# BPB_v16.net
KiCad netlist of a schematic drawn in EAGLE
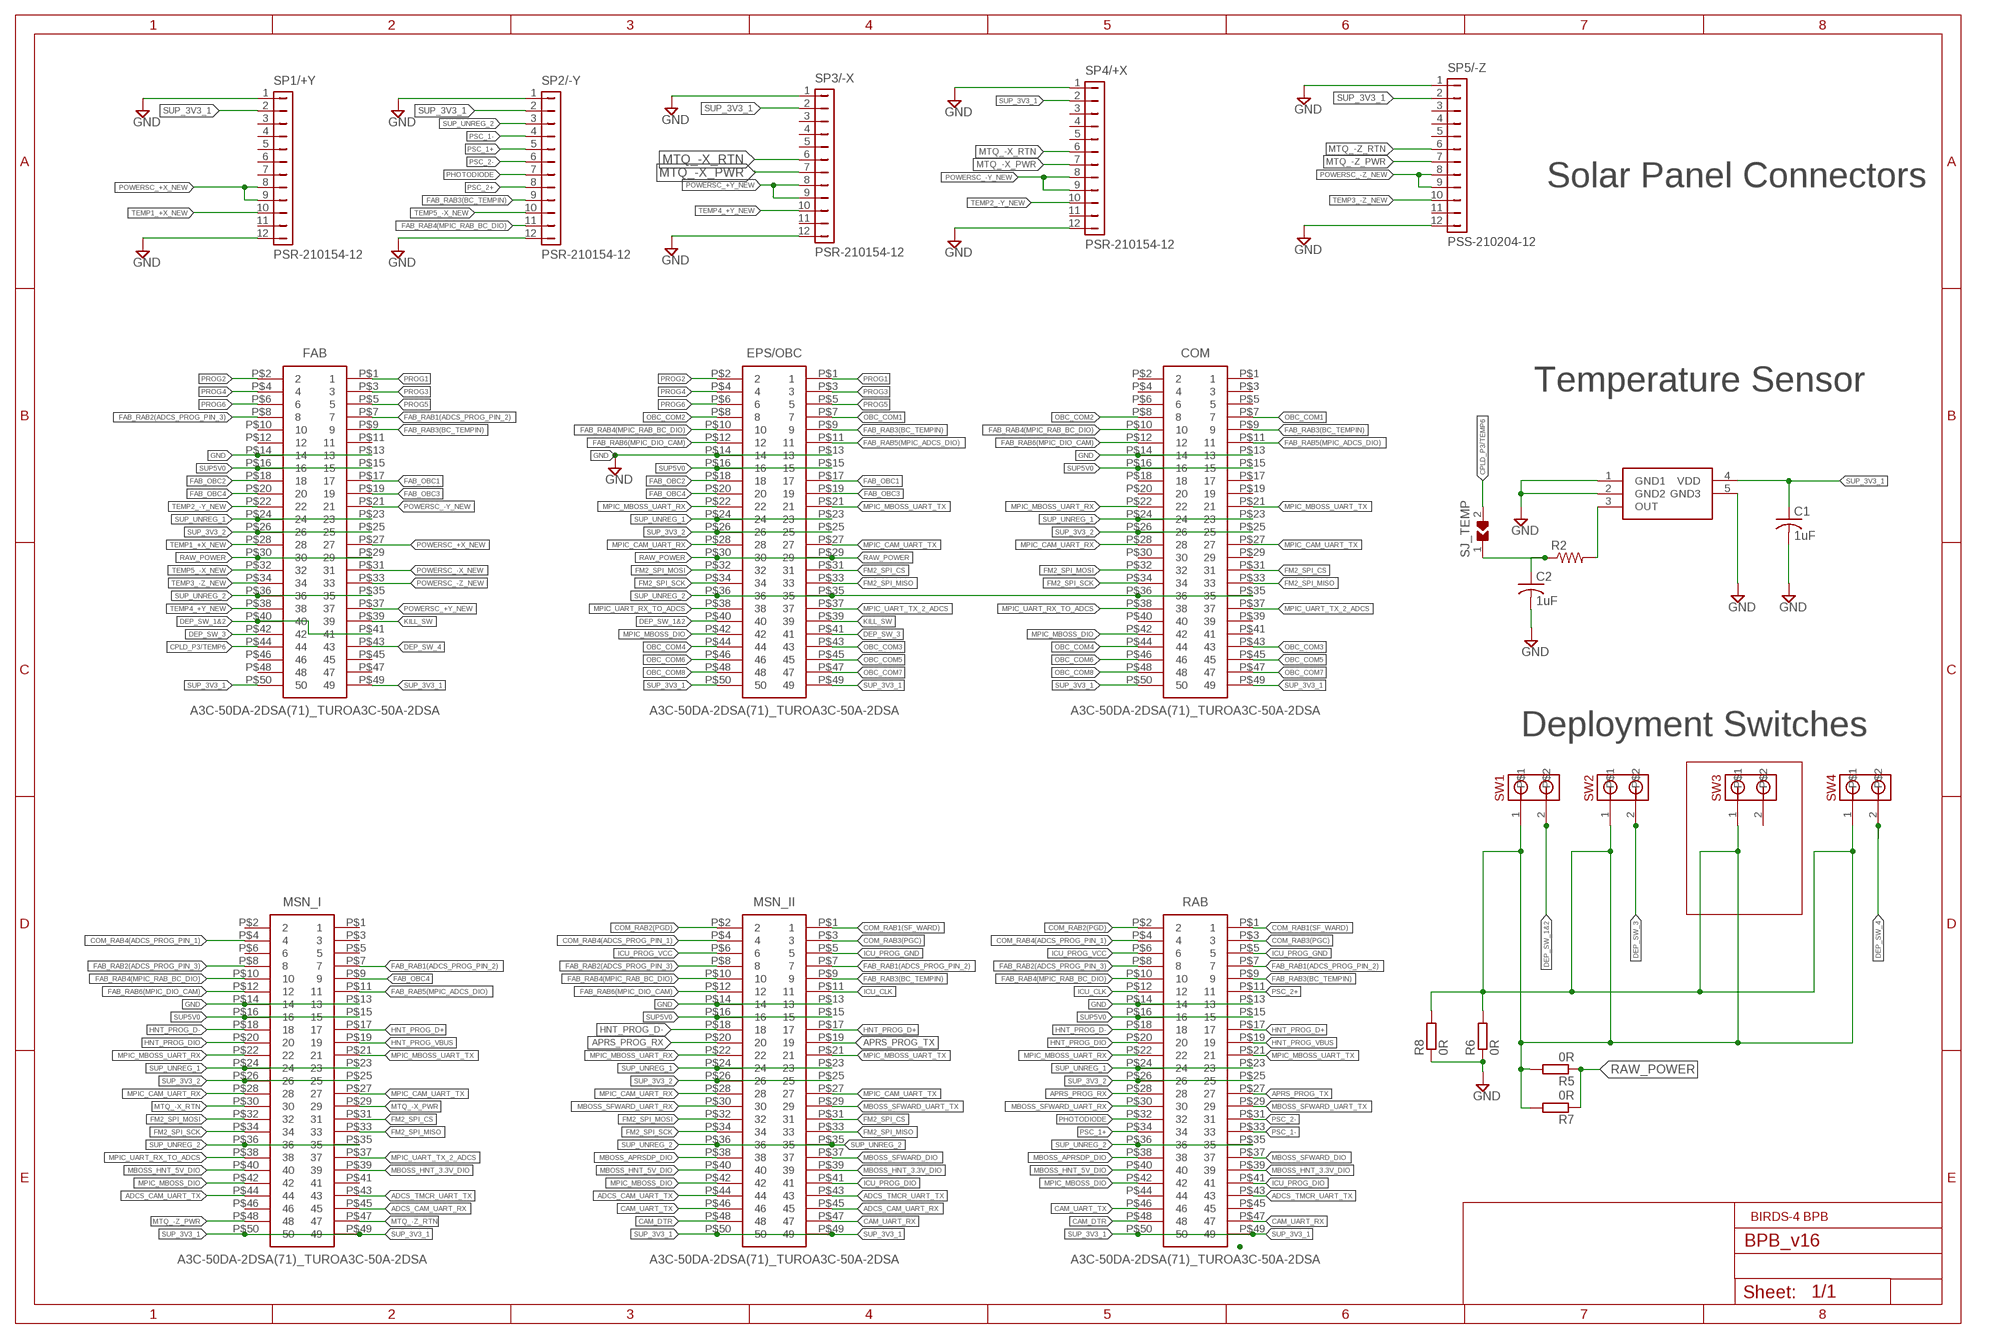
[diagram p0: schematic, sheet 1]

(export (version "E")
  (design (tool "Eeschema 10.0.6"))
  (components
    (comp (ref "C1")
      (value "1uF")
      (footprint "eagle-import:C0603")
      (libsource (lib "eagle-import") (part "C-USC0603"))
    )
    (comp (ref "C2")
      (value "1uF")
      (footprint "eagle-import:C0603")
      (libsource (lib "eagle-import") (part "C-USC0603"))
    )
    (comp (ref "COM")
      (value "A3C-50DA-2DSA(71)_TUROA3C-50A-2DSA")
      (footprint "eagle-import:SHDR50W60P200_2X25_5000X400X44_TR")
      (libsource (lib "eagle-import") (part "A3C-50DA-2DSA(71)_TUROA3C-50A-2DSA"))
    )
    (comp (ref "EPS/OBC")
      (value "A3C-50DA-2DSA(71)_TUROA3C-50A-2DSA")
      (footprint "eagle-import:SHDR50W60P200_2X25_5000X400X44_TR")
      (libsource (lib "eagle-import") (part "A3C-50DA-2DSA(71)_TUROA3C-50A-2DSA"))
    )
    (comp (ref "FAB")
      (value "A3C-50DA-2DSA(71)_TUROA3C-50A-2DSA")
      (footprint "eagle-import:SHDR50W60P200_2X25_5000X400X44_TR")
      (libsource (lib "eagle-import") (part "A3C-50DA-2DSA(71)_TUROA3C-50A-2DSA"))
    )
    (comp (ref "MSN_I")
      (value "A3C-50DA-2DSA(71)_TUROA3C-50A-2DSA")
      (footprint "eagle-import:SHDR50W60P200_2X25_5000X400X44_TR")
      (libsource (lib "eagle-import") (part "A3C-50DA-2DSA(71)_TUROA3C-50A-2DSA"))
    )
    (comp (ref "MSN_II")
      (value "A3C-50DA-2DSA(71)_TUROA3C-50A-2DSA")
      (footprint "eagle-import:SHDR50W60P200_2X25_5000X400X44_TR")
      (libsource (lib "eagle-import") (part "A3C-50DA-2DSA(71)_TUROA3C-50A-2DSA"))
    )
    (comp (ref "R2")
      (value "R-US_R0402")
      (footprint "eagle-import:R0402")
      (libsource (lib "eagle-import") (part "R-US_R0402"))
    )
    (comp (ref "R5")
      (value "0R")
      (footprint "eagle-import:R3216")
      (libsource (lib "eagle-import") (part "RR3216"))
    )
    (comp (ref "R6")
      (value "0R")
      (footprint "eagle-import:R3216")
      (libsource (lib "eagle-import") (part "RR3216"))
    )
    (comp (ref "R7")
      (value "0R")
      (footprint "eagle-import:R3216")
      (libsource (lib "eagle-import") (part "RR3216"))
    )
    (comp (ref "R8")
      (value "0R")
      (footprint "eagle-import:R3216")
      (libsource (lib "eagle-import") (part "RR3216"))
    )
    (comp (ref "RAB")
      (value "A3C-50DA-2DSA(71)_TUROA3C-50A-2DSA")
      (footprint "eagle-import:SHDR50W60P200_2X25_5000X400X44_TR")
      (libsource (lib "eagle-import") (part "A3C-50DA-2DSA(71)_TUROA3C-50A-2DSA"))
    )
    (comp (ref "SJ_TEMP")
      (value "SJ_BY_TURO")
      (footprint "eagle-import:SJ_TURO")
      (libsource (lib "eagle-import") (part "SJ_BY_TURO"))
    )
    (comp (ref "SP1/+Y")
      (value "PSR-210154-12")
      (footprint "eagle-import:PIN1X12_90")
      (libsource (lib "eagle-import") (part "PSR-210154-12"))
    )
    (comp (ref "SP2/-Y")
      (value "PSR-210154-12")
      (footprint "eagle-import:PIN1X12_90")
      (libsource (lib "eagle-import") (part "PSR-210154-12"))
    )
    (comp (ref "SP3/-X")
      (value "PSR-210154-12")
      (footprint "eagle-import:PIN1X12_90")
      (libsource (lib "eagle-import") (part "PSR-210154-12"))
    )
    (comp (ref "SP4/+X")
      (value "PSR-210154-12")
      (footprint "eagle-import:PIN1X12_90")
      (libsource (lib "eagle-import") (part "PSR-210154-12"))
    )
    (comp (ref "SP5/-Z")
      (value "PSS-210204-12")
      (footprint "eagle-import:PIN1X12")
      (libsource (lib "eagle-import") (part "PSS-210204-12"))
    )
    (comp (ref "SW1")
      (value "MOLEX-CONN-2-0554600272")
      (footprint "eagle-import:MOLEX-CONN-2-BIRDS")
      (libsource (lib "eagle-import") (part "MOLEX-CONN-2-0554600272"))
    )
    (comp (ref "SW2")
      (value "MOLEX-CONN-2-0554600272")
      (footprint "eagle-import:MOLEX-CONN-2-BIRDS")
      (libsource (lib "eagle-import") (part "MOLEX-CONN-2-0554600272"))
    )
    (comp (ref "SW3")
      (value "MOLEX-CONN-2-0554600272")
      (footprint "eagle-import:MOLEX-CONN-2-BIRDS")
      (libsource (lib "eagle-import") (part "MOLEX-CONN-2-0554600272"))
    )
    (comp (ref "SW4")
      (value "MOLEX-CONN-2-0554600272")
      (footprint "eagle-import:MOLEX-CONN-2-BIRDS")
      (libsource (lib "eagle-import") (part "MOLEX-CONN-2-0554600272"))
    )
    (comp (ref "U$3")
      (value "LMT84DCKT")
      (footprint "eagle-import:SOT65P210X110-5N")
      (fields (field (name "RS_PART_NUMBER") "8115860"))
      (libsource (lib "eagle-import") (part "LMT84DCKT"))
    )
  )
  (nets
    (net (code "1") (name "ADCS_CAM_UART_RX") (class "Default")
      (node (ref "MSN_I") (pin "P$45") (pinfunction "45_P$45") (pintype "passive"))
      (node (ref "MSN_II") (pin "P$45") (pinfunction "45_P$45") (pintype "passive"))
    )
    (net (code "2") (name "ADCS_CAM_UART_TX") (class "Default")
      (node (ref "MSN_I") (pin "P$44") (pinfunction "44_P$44") (pintype "passive"))
      (node (ref "MSN_II") (pin "P$44") (pinfunction "44_P$44") (pintype "passive"))
    )
    (net (code "3") (name "ADCS_TMCR_UART_TX") (class "Default")
      (node (ref "MSN_I") (pin "P$43") (pinfunction "43_P$43") (pintype "passive"))
      (node (ref "MSN_II") (pin "P$43") (pinfunction "43_P$43") (pintype "passive"))
      (node (ref "RAB") (pin "P$43") (pinfunction "43_P$43") (pintype "passive"))
    )
    (net (code "4") (name "APRS_PROG_RX") (class "Default")
      (node (ref "MSN_II") (pin "P$20") (pinfunction "20_P$20") (pintype "passive"))
      (node (ref "RAB") (pin "P$28") (pinfunction "28_P$28") (pintype "passive"))
    )
    (net (code "5") (name "APRS_PROG_TX") (class "Default")
      (node (ref "MSN_II") (pin "P$19") (pinfunction "19_P$19") (pintype "passive"))
      (node (ref "RAB") (pin "P$27") (pinfunction "27_P$27") (pintype "passive"))
    )
    (net (code "6") (name "CAM_DTR") (class "Default")
      (node (ref "MSN_II") (pin "P$48") (pinfunction "48_P$48") (pintype "passive"))
      (node (ref "RAB") (pin "P$48") (pinfunction "48_P$48") (pintype "passive"))
    )
    (net (code "7") (name "CAM_UART_RX") (class "Default")
      (node (ref "MSN_II") (pin "P$47") (pinfunction "47_P$47") (pintype "passive"))
      (node (ref "RAB") (pin "P$47") (pinfunction "47_P$47") (pintype "passive"))
    )
    (net (code "8") (name "CAM_UART_TX") (class "Default")
      (node (ref "MSN_II") (pin "P$46") (pinfunction "46_P$46") (pintype "passive"))
      (node (ref "RAB") (pin "P$46") (pinfunction "46_P$46") (pintype "passive"))
    )
    (net (code "9") (name "COM_RAB1(SF_WARD)") (class "Default")
      (node (ref "MSN_II") (pin "P$1") (pinfunction "1_P$1") (pintype "passive"))
      (node (ref "RAB") (pin "P$1") (pinfunction "1_P$1") (pintype "passive"))
    )
    (net (code "10") (name "COM_RAB2(PGD)") (class "Default")
      (node (ref "MSN_II") (pin "P$2") (pinfunction "2_P$2") (pintype "passive"))
      (node (ref "RAB") (pin "P$2") (pinfunction "2_P$2") (pintype "passive"))
    )
    (net (code "11") (name "COM_RAB3(PGC)") (class "Default")
      (node (ref "MSN_II") (pin "P$3") (pinfunction "3_P$3") (pintype "passive"))
      (node (ref "RAB") (pin "P$3") (pinfunction "3_P$3") (pintype "passive"))
    )
    (net (code "12") (name "COM_RAB4(ADCS_PROG_PIN_1)") (class "Default")
      (node (ref "MSN_I") (pin "P$4") (pinfunction "4_P$4") (pintype "passive"))
      (node (ref "MSN_II") (pin "P$4") (pinfunction "4_P$4") (pintype "passive"))
      (node (ref "RAB") (pin "P$4") (pinfunction "4_P$4") (pintype "passive"))
    )
    (net (code "13") (name "CPLD_P3{slash}TEMP6") (class "Default")
      (node (ref "FAB") (pin "P$44") (pinfunction "44_P$44") (pintype "passive"))
      (node (ref "SJ_TEMP") (pin "2") (pinfunction "2_2") (pintype "passive"))
    )
    (net (code "14") (name "DEP_SW_1&2") (class "Default")
      (node (ref "EPS/OBC") (pin "P$40") (pinfunction "40_P$40") (pintype "passive"))
      (node (ref "FAB") (pin "P$40") (pinfunction "40_P$40") (pintype "passive"))
      (node (ref "FAB") (pin "P$41") (pinfunction "41_P$41") (pintype "passive"))
      (node (ref "SW1") (pin "2") (pinfunction "P$2_2") (pintype "bidirectional"))
    )
    (net (code "15") (name "DEP_SW_3") (class "Default")
      (node (ref "EPS/OBC") (pin "P$41") (pinfunction "41_P$41") (pintype "passive"))
      (node (ref "FAB") (pin "P$42") (pinfunction "42_P$42") (pintype "passive"))
      (node (ref "SW2") (pin "2") (pinfunction "P$2_2") (pintype "bidirectional"))
    )
    (net (code "16") (name "DEP_SW_4") (class "Default")
      (node (ref "FAB") (pin "P$43") (pinfunction "43_P$43") (pintype "passive"))
      (node (ref "SW4") (pin "2") (pinfunction "P$2_2") (pintype "bidirectional"))
    )
    (net (code "17") (name "FAB_OBC1") (class "Default")
      (node (ref "EPS/OBC") (pin "P$17") (pinfunction "17_P$17") (pintype "passive"))
      (node (ref "FAB") (pin "P$17") (pinfunction "17_P$17") (pintype "passive"))
    )
    (net (code "18") (name "FAB_OBC2") (class "Default")
      (node (ref "EPS/OBC") (pin "P$18") (pinfunction "18_P$18") (pintype "passive"))
      (node (ref "FAB") (pin "P$18") (pinfunction "18_P$18") (pintype "passive"))
    )
    (net (code "19") (name "FAB_OBC3") (class "Default")
      (node (ref "EPS/OBC") (pin "P$19") (pinfunction "19_P$19") (pintype "passive"))
      (node (ref "FAB") (pin "P$19") (pinfunction "19_P$19") (pintype "passive"))
    )
    (net (code "20") (name "FAB_OBC4") (class "Default")
      (node (ref "EPS/OBC") (pin "P$20") (pinfunction "20_P$20") (pintype "passive"))
      (node (ref "FAB") (pin "P$20") (pinfunction "20_P$20") (pintype "passive"))
      (node (ref "MSN_I") (pin "P$9") (pinfunction "9_P$9") (pintype "passive"))
    )
    (net (code "21") (name "FAB_RAB1(ADCS_PROG_PIN_2)") (class "Default")
      (node (ref "FAB") (pin "P$7") (pinfunction "7_P$7") (pintype "passive"))
      (node (ref "MSN_I") (pin "P$7") (pinfunction "7_P$7") (pintype "passive"))
      (node (ref "MSN_II") (pin "P$7") (pinfunction "7_P$7") (pintype "passive"))
      (node (ref "RAB") (pin "P$7") (pinfunction "7_P$7") (pintype "passive"))
    )
    (net (code "22") (name "FAB_RAB2(ADCS_PROG_PIN_3)") (class "Default")
      (node (ref "FAB") (pin "P$8") (pinfunction "8_P$8") (pintype "passive"))
      (node (ref "MSN_I") (pin "P$8") (pinfunction "8_P$8") (pintype "passive"))
      (node (ref "MSN_II") (pin "P$8") (pinfunction "8_P$8") (pintype "passive"))
      (node (ref "RAB") (pin "P$8") (pinfunction "8_P$8") (pintype "passive"))
    )
    (net (code "23") (name "FAB_RAB3(BC_TEMPIN)") (class "Default")
      (node (ref "COM") (pin "P$9") (pinfunction "9_P$9") (pintype "passive"))
      (node (ref "EPS/OBC") (pin "P$9") (pinfunction "9_P$9") (pintype "passive"))
      (node (ref "FAB") (pin "P$9") (pinfunction "9_P$9") (pintype "passive"))
      (node (ref "MSN_II") (pin "P$9") (pinfunction "9_P$9") (pintype "passive"))
      (node (ref "RAB") (pin "P$9") (pinfunction "9_P$9") (pintype "passive"))
      (node (ref "SP2/-Y") (pin "9") (pinfunction "9_9") (pintype "passive"))
    )
    (net (code "24") (name "FAB_RAB4(MPIC_RAB_BC_DIO)") (class "Default")
      (node (ref "COM") (pin "P$10") (pinfunction "10_P$10") (pintype "passive"))
      (node (ref "EPS/OBC") (pin "P$10") (pinfunction "10_P$10") (pintype "passive"))
      (node (ref "MSN_I") (pin "P$10") (pinfunction "10_P$10") (pintype "passive"))
      (node (ref "MSN_II") (pin "P$10") (pinfunction "10_P$10") (pintype "passive"))
      (node (ref "RAB") (pin "P$10") (pinfunction "10_P$10") (pintype "passive"))
      (node (ref "SP2/-Y") (pin "11") (pinfunction "11_11") (pintype "passive"))
    )
    (net (code "25") (name "FAB_RAB5(MPIC_ADCS_DIO)") (class "Default")
      (node (ref "COM") (pin "P$11") (pinfunction "11_P$11") (pintype "passive"))
      (node (ref "EPS/OBC") (pin "P$11") (pinfunction "11_P$11") (pintype "passive"))
      (node (ref "MSN_I") (pin "P$11") (pinfunction "11_P$11") (pintype "passive"))
    )
    (net (code "26") (name "FAB_RAB6(MPIC_DIO_CAM)") (class "Default")
      (node (ref "COM") (pin "P$12") (pinfunction "12_P$12") (pintype "passive"))
      (node (ref "EPS/OBC") (pin "P$12") (pinfunction "12_P$12") (pintype "passive"))
      (node (ref "MSN_I") (pin "P$12") (pinfunction "12_P$12") (pintype "passive"))
      (node (ref "MSN_II") (pin "P$12") (pinfunction "12_P$12") (pintype "passive"))
    )
    (net (code "27") (name "FM2_SPI_CS") (class "Default")
      (node (ref "COM") (pin "P$31") (pinfunction "31_P$31") (pintype "passive"))
      (node (ref "EPS/OBC") (pin "P$31") (pinfunction "31_P$31") (pintype "passive"))
      (node (ref "MSN_I") (pin "P$31") (pinfunction "31_P$31") (pintype "passive"))
      (node (ref "MSN_II") (pin "P$31") (pinfunction "31_P$31") (pintype "passive"))
    )
    (net (code "28") (name "FM2_SPI_MISO") (class "Default")
      (node (ref "COM") (pin "P$33") (pinfunction "33_P$33") (pintype "passive"))
      (node (ref "EPS/OBC") (pin "P$33") (pinfunction "33_P$33") (pintype "passive"))
      (node (ref "MSN_I") (pin "P$33") (pinfunction "33_P$33") (pintype "passive"))
      (node (ref "MSN_II") (pin "P$33") (pinfunction "33_P$33") (pintype "passive"))
    )
    (net (code "29") (name "FM2_SPI_MOSI") (class "Default")
      (node (ref "COM") (pin "P$32") (pinfunction "32_P$32") (pintype "passive"))
      (node (ref "EPS/OBC") (pin "P$32") (pinfunction "32_P$32") (pintype "passive"))
      (node (ref "MSN_I") (pin "P$32") (pinfunction "32_P$32") (pintype "passive"))
      (node (ref "MSN_II") (pin "P$32") (pinfunction "32_P$32") (pintype "passive"))
    )
    (net (code "30") (name "FM2_SPI_SCK") (class "Default")
      (node (ref "COM") (pin "P$34") (pinfunction "34_P$34") (pintype "passive"))
      (node (ref "EPS/OBC") (pin "P$34") (pinfunction "34_P$34") (pintype "passive"))
      (node (ref "MSN_I") (pin "P$34") (pinfunction "34_P$34") (pintype "passive"))
      (node (ref "MSN_II") (pin "P$34") (pinfunction "34_P$34") (pintype "passive"))
    )
    (net (code "31") (name "GND") (class "Default")
      (node (ref "C1") (pin "2") (pinfunction "2_2") (pintype "passive"))
      (node (ref "C2") (pin "2") (pinfunction "2_2") (pintype "passive"))
      (node (ref "COM") (pin "P$13") (pinfunction "13_P$13") (pintype "passive"))
      (node (ref "COM") (pin "P$14") (pinfunction "14_P$14") (pintype "passive"))
      (node (ref "EPS/OBC") (pin "P$13") (pinfunction "13_P$13") (pintype "passive"))
      (node (ref "EPS/OBC") (pin "P$14") (pinfunction "14_P$14") (pintype "passive"))
      (node (ref "FAB") (pin "P$13") (pinfunction "13_P$13") (pintype "passive"))
      (node (ref "FAB") (pin "P$14") (pinfunction "14_P$14") (pintype "passive"))
      (node (ref "MSN_I") (pin "P$13") (pinfunction "13_P$13") (pintype "passive"))
      (node (ref "MSN_I") (pin "P$14") (pinfunction "14_P$14") (pintype "passive"))
      (node (ref "MSN_II") (pin "P$13") (pinfunction "13_P$13") (pintype "passive"))
      (node (ref "MSN_II") (pin "P$14") (pinfunction "14_P$14") (pintype "passive"))
      (node (ref "R6") (pin "1") (pinfunction "1_1") (pintype "passive"))
      (node (ref "R8") (pin "1") (pinfunction "1_1") (pintype "passive"))
      (node (ref "RAB") (pin "P$13") (pinfunction "13_P$13") (pintype "passive"))
      (node (ref "RAB") (pin "P$14") (pinfunction "14_P$14") (pintype "passive"))
      (node (ref "SP1/+Y") (pin "1") (pinfunction "1_1") (pintype "passive"))
      (node (ref "SP1/+Y") (pin "12") (pinfunction "12_12") (pintype "passive"))
      (node (ref "SP2/-Y") (pin "1") (pinfunction "1_1") (pintype "passive"))
      (node (ref "SP2/-Y") (pin "12") (pinfunction "12_12") (pintype "passive"))
      (node (ref "SP3/-X") (pin "1") (pinfunction "1_1") (pintype "passive"))
      (node (ref "SP3/-X") (pin "12") (pinfunction "12_12") (pintype "passive"))
      (node (ref "SP4/+X") (pin "1") (pinfunction "1_1") (pintype "passive"))
      (node (ref "SP4/+X") (pin "12") (pinfunction "12_12") (pintype "passive"))
      (node (ref "SP5/-Z") (pin "1") (pinfunction "1_1") (pintype "passive"))
      (node (ref "SP5/-Z") (pin "12") (pinfunction "12_12") (pintype "passive"))
      (node (ref "U$3") (pin "1") (pinfunction "GND1_1") (pintype "power_in"))
      (node (ref "U$3") (pin "2") (pinfunction "GND2_2") (pintype "power_in"))
      (node (ref "U$3") (pin "5") (pinfunction "GND3_5") (pintype "power_in"))
    )
    (net (code "32") (name "HNT_PROG_D+") (class "Default")
      (node (ref "MSN_I") (pin "P$17") (pinfunction "17_P$17") (pintype "passive"))
      (node (ref "MSN_II") (pin "P$17") (pinfunction "17_P$17") (pintype "passive"))
      (node (ref "RAB") (pin "P$17") (pinfunction "17_P$17") (pintype "passive"))
    )
    (net (code "33") (name "HNT_PROG_D-") (class "Default")
      (node (ref "MSN_I") (pin "P$18") (pinfunction "18_P$18") (pintype "passive"))
      (node (ref "MSN_II") (pin "P$18") (pinfunction "18_P$18") (pintype "passive"))
      (node (ref "RAB") (pin "P$18") (pinfunction "18_P$18") (pintype "passive"))
    )
    (net (code "34") (name "HNT_PROG_DIO") (class "Default")
      (node (ref "MSN_I") (pin "P$20") (pinfunction "20_P$20") (pintype "passive"))
      (node (ref "RAB") (pin "P$20") (pinfunction "20_P$20") (pintype "passive"))
    )
    (net (code "35") (name "HNT_PROG_VBUS") (class "Default")
      (node (ref "MSN_I") (pin "P$19") (pinfunction "19_P$19") (pintype "passive"))
      (node (ref "RAB") (pin "P$19") (pinfunction "19_P$19") (pintype "passive"))
    )
    (net (code "36") (name "ICU_CLK") (class "Default")
      (node (ref "MSN_II") (pin "P$11") (pinfunction "11_P$11") (pintype "passive"))
      (node (ref "RAB") (pin "P$12") (pinfunction "12_P$12") (pintype "passive"))
    )
    (net (code "37") (name "ICU_PROG_DIO") (class "Default")
      (node (ref "MSN_II") (pin "P$41") (pinfunction "41_P$41") (pintype "passive"))
      (node (ref "RAB") (pin "P$41") (pinfunction "41_P$41") (pintype "passive"))
    )
    (net (code "38") (name "ICU_PROG_GND") (class "Default")
      (node (ref "MSN_II") (pin "P$5") (pinfunction "5_P$5") (pintype "passive"))
      (node (ref "RAB") (pin "P$5") (pinfunction "5_P$5") (pintype "passive"))
    )
    (net (code "39") (name "ICU_PROG_VCC") (class "Default")
      (node (ref "MSN_II") (pin "P$6") (pinfunction "6_P$6") (pintype "passive"))
      (node (ref "RAB") (pin "P$6") (pinfunction "6_P$6") (pintype "passive"))
    )
    (net (code "40") (name "KILL_SW") (class "Default")
      (node (ref "EPS/OBC") (pin "P$39") (pinfunction "39_P$39") (pintype "passive"))
      (node (ref "FAB") (pin "P$39") (pinfunction "39_P$39") (pintype "passive"))
    )
    (net (code "41") (name "MBOSS_APRSDP_DIO") (class "Default")
      (node (ref "MSN_II") (pin "P$38") (pinfunction "38_P$38") (pintype "passive"))
      (node (ref "RAB") (pin "P$38") (pinfunction "38_P$38") (pintype "passive"))
    )
    (net (code "42") (name "MBOSS_HNT_3.3V_DIO") (class "Default")
      (node (ref "MSN_I") (pin "P$39") (pinfunction "39_P$39") (pintype "passive"))
      (node (ref "MSN_II") (pin "P$39") (pinfunction "39_P$39") (pintype "passive"))
      (node (ref "RAB") (pin "P$39") (pinfunction "39_P$39") (pintype "passive"))
    )
    (net (code "43") (name "MBOSS_HNT_5V_DIO") (class "Default")
      (node (ref "MSN_I") (pin "P$40") (pinfunction "40_P$40") (pintype "passive"))
      (node (ref "MSN_II") (pin "P$40") (pinfunction "40_P$40") (pintype "passive"))
      (node (ref "RAB") (pin "P$40") (pinfunction "40_P$40") (pintype "passive"))
    )
    (net (code "44") (name "MBOSS_SFWARD_DIO") (class "Default")
      (node (ref "MSN_II") (pin "P$37") (pinfunction "37_P$37") (pintype "passive"))
      (node (ref "RAB") (pin "P$37") (pinfunction "37_P$37") (pintype "passive"))
    )
    (net (code "45") (name "MBOSS_SFWARD_UART_RX") (class "Default")
      (node (ref "MSN_II") (pin "P$30") (pinfunction "30_P$30") (pintype "passive"))
      (node (ref "RAB") (pin "P$30") (pinfunction "30_P$30") (pintype "passive"))
    )
    (net (code "46") (name "MBOSS_SFWARD_UART_TX") (class "Default")
      (node (ref "MSN_II") (pin "P$29") (pinfunction "29_P$29") (pintype "passive"))
      (node (ref "RAB") (pin "P$29") (pinfunction "29_P$29") (pintype "passive"))
    )
    (net (code "47") (name "MPIC_CAM_UART_RX") (class "Default")
      (node (ref "COM") (pin "P$28") (pinfunction "28_P$28") (pintype "passive"))
      (node (ref "EPS/OBC") (pin "P$28") (pinfunction "28_P$28") (pintype "passive"))
      (node (ref "MSN_I") (pin "P$28") (pinfunction "28_P$28") (pintype "passive"))
      (node (ref "MSN_II") (pin "P$28") (pinfunction "28_P$28") (pintype "passive"))
    )
    (net (code "48") (name "MPIC_CAM_UART_TX") (class "Default")
      (node (ref "COM") (pin "P$27") (pinfunction "27_P$27") (pintype "passive"))
      (node (ref "EPS/OBC") (pin "P$27") (pinfunction "27_P$27") (pintype "passive"))
      (node (ref "MSN_I") (pin "P$27") (pinfunction "27_P$27") (pintype "passive"))
      (node (ref "MSN_II") (pin "P$27") (pinfunction "27_P$27") (pintype "passive"))
    )
    (net (code "49") (name "MPIC_MBOSS_DIO") (class "Default")
      (node (ref "COM") (pin "P$42") (pinfunction "42_P$42") (pintype "passive"))
      (node (ref "EPS/OBC") (pin "P$42") (pinfunction "42_P$42") (pintype "passive"))
      (node (ref "MSN_I") (pin "P$42") (pinfunction "42_P$42") (pintype "passive"))
      (node (ref "MSN_II") (pin "P$42") (pinfunction "42_P$42") (pintype "passive"))
      (node (ref "RAB") (pin "P$42") (pinfunction "42_P$42") (pintype "passive"))
    )
    (net (code "50") (name "MPIC_MBOSS_UART_RX") (class "Default")
      (node (ref "COM") (pin "P$22") (pinfunction "22_P$22") (pintype "passive"))
      (node (ref "EPS/OBC") (pin "P$22") (pinfunction "22_P$22") (pintype "passive"))
      (node (ref "MSN_I") (pin "P$22") (pinfunction "22_P$22") (pintype "passive"))
      (node (ref "MSN_II") (pin "P$22") (pinfunction "22_P$22") (pintype "passive"))
      (node (ref "RAB") (pin "P$22") (pinfunction "22_P$22") (pintype "passive"))
    )
    (net (code "51") (name "MPIC_MBOSS_UART_TX") (class "Default")
      (node (ref "COM") (pin "P$21") (pinfunction "21_P$21") (pintype "passive"))
      (node (ref "EPS/OBC") (pin "P$21") (pinfunction "21_P$21") (pintype "passive"))
      (node (ref "MSN_I") (pin "P$21") (pinfunction "21_P$21") (pintype "passive"))
      (node (ref "MSN_II") (pin "P$21") (pinfunction "21_P$21") (pintype "passive"))
      (node (ref "RAB") (pin "P$21") (pinfunction "21_P$21") (pintype "passive"))
    )
    (net (code "52") (name "MPIC_UART_RX_TO_ADCS") (class "Default")
      (node (ref "COM") (pin "P$38") (pinfunction "38_P$38") (pintype "passive"))
      (node (ref "EPS/OBC") (pin "P$38") (pinfunction "38_P$38") (pintype "passive"))
      (node (ref "MSN_I") (pin "P$38") (pinfunction "38_P$38") (pintype "passive"))
    )
    (net (code "53") (name "MPIC_UART_TX_2_ADCS") (class "Default")
      (node (ref "COM") (pin "P$37") (pinfunction "37_P$37") (pintype "passive"))
      (node (ref "EPS/OBC") (pin "P$37") (pinfunction "37_P$37") (pintype "passive"))
      (node (ref "MSN_I") (pin "P$37") (pinfunction "37_P$37") (pintype "passive"))
    )
    (net (code "54") (name "MTQ_-X_PWR") (class "Default")
      (node (ref "MSN_I") (pin "P$29") (pinfunction "29_P$29") (pintype "passive"))
      (node (ref "SP3/-X") (pin "7") (pinfunction "7_7") (pintype "passive"))
      (node (ref "SP4/+X") (pin "7") (pinfunction "7_7") (pintype "passive"))
    )
    (net (code "55") (name "MTQ_-X_RTN") (class "Default")
      (node (ref "MSN_I") (pin "P$30") (pinfunction "30_P$30") (pintype "passive"))
      (node (ref "SP3/-X") (pin "6") (pinfunction "6_6") (pintype "passive"))
      (node (ref "SP4/+X") (pin "6") (pinfunction "6_6") (pintype "passive"))
    )
    (net (code "56") (name "MTQ_-Z_PWR") (class "Default")
      (node (ref "MSN_I") (pin "P$48") (pinfunction "48_P$48") (pintype "passive"))
      (node (ref "SP5/-Z") (pin "7") (pinfunction "7_7") (pintype "passive"))
    )
    (net (code "57") (name "MTQ_-Z_RTN") (class "Default")
      (node (ref "MSN_I") (pin "P$47") (pinfunction "47_P$47") (pintype "passive"))
      (node (ref "SP5/-Z") (pin "6") (pinfunction "6_6") (pintype "passive"))
    )
    (net (code "58") (name "Net-(C2-Pad1)") (class "Default")
      (node (ref "C2") (pin "1") (pinfunction "1_1") (pintype "passive"))
      (node (ref "R2") (pin "1") (pinfunction "1_1") (pintype "passive"))
      (node (ref "SJ_TEMP") (pin "1") (pinfunction "1_1") (pintype "passive"))
    )
    (net (code "59") (name "Net-(SW1-P$1)") (class "Default")
      (node (ref "R5") (pin "2") (pinfunction "2_2") (pintype "passive"))
      (node (ref "R6") (pin "2") (pinfunction "2_2") (pintype "passive"))
      (node (ref "R7") (pin "2") (pinfunction "2_2") (pintype "passive"))
      (node (ref "R8") (pin "2") (pinfunction "2_2") (pintype "passive"))
      (node (ref "SW1") (pin "1") (pinfunction "P$1_1") (pintype "bidirectional"))
      (node (ref "SW2") (pin "1") (pinfunction "P$1_1") (pintype "bidirectional"))
      (node (ref "SW3") (pin "1") (pinfunction "P$1_1") (pintype "bidirectional"))
      (node (ref "SW4") (pin "1") (pinfunction "P$1_1") (pintype "bidirectional"))
    )
    (net (code "60") (name "Net-(U$3-OUT)") (class "Default")
      (node (ref "R2") (pin "2") (pinfunction "2_2") (pintype "passive"))
      (node (ref "U$3") (pin "3") (pinfunction "OUT_3") (pintype "output"))
    )
    (net (code "61") (name "OBC_COM1") (class "Default")
      (node (ref "COM") (pin "P$7") (pinfunction "7_P$7") (pintype "passive"))
      (node (ref "EPS/OBC") (pin "P$7") (pinfunction "7_P$7") (pintype "passive"))
    )
    (net (code "62") (name "OBC_COM2") (class "Default")
      (node (ref "COM") (pin "P$8") (pinfunction "8_P$8") (pintype "passive"))
      (node (ref "EPS/OBC") (pin "P$8") (pinfunction "8_P$8") (pintype "passive"))
    )
    (net (code "63") (name "OBC_COM3") (class "Default")
      (node (ref "COM") (pin "P$43") (pinfunction "43_P$43") (pintype "passive"))
      (node (ref "EPS/OBC") (pin "P$43") (pinfunction "43_P$43") (pintype "passive"))
    )
    (net (code "64") (name "OBC_COM4") (class "Default")
      (node (ref "COM") (pin "P$44") (pinfunction "44_P$44") (pintype "passive"))
      (node (ref "EPS/OBC") (pin "P$44") (pinfunction "44_P$44") (pintype "passive"))
    )
    (net (code "65") (name "OBC_COM5") (class "Default")
      (node (ref "COM") (pin "P$45") (pinfunction "45_P$45") (pintype "passive"))
      (node (ref "EPS/OBC") (pin "P$45") (pinfunction "45_P$45") (pintype "passive"))
    )
    (net (code "66") (name "OBC_COM6") (class "Default")
      (node (ref "COM") (pin "P$46") (pinfunction "46_P$46") (pintype "passive"))
      (node (ref "EPS/OBC") (pin "P$46") (pinfunction "46_P$46") (pintype "passive"))
    )
    (net (code "67") (name "OBC_COM7") (class "Default")
      (node (ref "COM") (pin "P$47") (pinfunction "47_P$47") (pintype "passive"))
      (node (ref "EPS/OBC") (pin "P$47") (pinfunction "47_P$47") (pintype "passive"))
    )
    (net (code "68") (name "OBC_COM8") (class "Default")
      (node (ref "COM") (pin "P$48") (pinfunction "48_P$48") (pintype "passive"))
      (node (ref "EPS/OBC") (pin "P$48") (pinfunction "48_P$48") (pintype "passive"))
    )
    (net (code "69") (name "PHOTODIODE") (class "Default")
      (node (ref "RAB") (pin "P$32") (pinfunction "32_P$32") (pintype "passive"))
      (node (ref "SP2/-Y") (pin "7") (pinfunction "7_7") (pintype "passive"))
    )
    (net (code "70") (name "POWERSC_+X_NEW") (class "Default")
      (node (ref "FAB") (pin "P$27") (pinfunction "27_P$27") (pintype "passive"))
      (node (ref "SP1/+Y") (pin "8") (pinfunction "8_8") (pintype "passive"))
      (node (ref "SP1/+Y") (pin "9") (pinfunction "9_9") (pintype "passive"))
    )
    (net (code "71") (name "POWERSC_+Y_NEW") (class "Default")
      (node (ref "FAB") (pin "P$37") (pinfunction "37_P$37") (pintype "passive"))
      (node (ref "SP3/-X") (pin "8") (pinfunction "8_8") (pintype "passive"))
      (node (ref "SP3/-X") (pin "9") (pinfunction "9_9") (pintype "passive"))
    )
    (net (code "72") (name "POWERSC_-X_NEW") (class "Default")
      (node (ref "FAB") (pin "P$31") (pinfunction "31_P$31") (pintype "passive"))
    )
    (net (code "73") (name "POWERSC_-Y_NEW") (class "Default")
      (node (ref "FAB") (pin "P$21") (pinfunction "21_P$21") (pintype "passive"))
      (node (ref "SP4/+X") (pin "8") (pinfunction "8_8") (pintype "passive"))
      (node (ref "SP4/+X") (pin "9") (pinfunction "9_9") (pintype "passive"))
    )
    (net (code "74") (name "POWERSC_-Z_NEW") (class "Default")
      (node (ref "FAB") (pin "P$33") (pinfunction "33_P$33") (pintype "passive"))
      (node (ref "SP5/-Z") (pin "8") (pinfunction "8_8") (pintype "passive"))
      (node (ref "SP5/-Z") (pin "9") (pinfunction "9_9") (pintype "passive"))
    )
    (net (code "75") (name "PROG1") (class "Default")
      (node (ref "EPS/OBC") (pin "P$1") (pinfunction "1_P$1") (pintype "passive"))
      (node (ref "FAB") (pin "P$1") (pinfunction "1_P$1") (pintype "passive"))
    )
    (net (code "76") (name "PROG2") (class "Default")
      (node (ref "EPS/OBC") (pin "P$2") (pinfunction "2_P$2") (pintype "passive"))
      (node (ref "FAB") (pin "P$2") (pinfunction "2_P$2") (pintype "passive"))
    )
    (net (code "77") (name "PROG3") (class "Default")
      (node (ref "EPS/OBC") (pin "P$3") (pinfunction "3_P$3") (pintype "passive"))
      (node (ref "FAB") (pin "P$3") (pinfunction "3_P$3") (pintype "passive"))
    )
    (net (code "78") (name "PROG4") (class "Default")
      (node (ref "EPS/OBC") (pin "P$4") (pinfunction "4_P$4") (pintype "passive"))
      (node (ref "FAB") (pin "P$4") (pinfunction "4_P$4") (pintype "passive"))
    )
    (net (code "79") (name "PROG5") (class "Default")
      (node (ref "EPS/OBC") (pin "P$5") (pinfunction "5_P$5") (pintype "passive"))
      (node (ref "FAB") (pin "P$5") (pinfunction "5_P$5") (pintype "passive"))
    )
    (net (code "80") (name "PROG6") (class "Default")
      (node (ref "EPS/OBC") (pin "P$6") (pinfunction "6_P$6") (pintype "passive"))
      (node (ref "FAB") (pin "P$6") (pinfunction "6_P$6") (pintype "passive"))
    )
    (net (code "81") (name "PSC_1+") (class "Default")
      (node (ref "RAB") (pin "P$34") (pinfunction "34_P$34") (pintype "passive"))
      (node (ref "SP2/-Y") (pin "5") (pinfunction "5_5") (pintype "passive"))
    )
    (net (code "82") (name "PSC_1-") (class "Default")
      (node (ref "RAB") (pin "P$33") (pinfunction "33_P$33") (pintype "passive"))
      (node (ref "SP2/-Y") (pin "4") (pinfunction "4_4") (pintype "passive"))
    )
    (net (code "83") (name "PSC_2+") (class "Default")
      (node (ref "RAB") (pin "P$11") (pinfunction "11_P$11") (pintype "passive"))
      (node (ref "SP2/-Y") (pin "8") (pinfunction "8_8") (pintype "passive"))
    )
    (net (code "84") (name "PSC_2-") (class "Default")
      (node (ref "RAB") (pin "P$31") (pinfunction "31_P$31") (pintype "passive"))
      (node (ref "SP2/-Y") (pin "6") (pinfunction "6_6") (pintype "passive"))
    )
    (net (code "85") (name "RAW_POWER") (class "Default")
      (node (ref "EPS/OBC") (pin "P$29") (pinfunction "29_P$29") (pintype "passive"))
      (node (ref "EPS/OBC") (pin "P$30") (pinfunction "30_P$30") (pintype "passive"))
      (node (ref "FAB") (pin "P$29") (pinfunction "29_P$29") (pintype "passive"))
      (node (ref "FAB") (pin "P$30") (pinfunction "30_P$30") (pintype "passive"))
      (node (ref "R5") (pin "1") (pinfunction "1_1") (pintype "passive"))
      (node (ref "R7") (pin "1") (pinfunction "1_1") (pintype "passive"))
    )
    (net (code "86") (name "SUP5V0") (class "Default")
      (node (ref "COM") (pin "P$15") (pinfunction "15_P$15") (pintype "passive"))
      (node (ref "COM") (pin "P$16") (pinfunction "16_P$16") (pintype "passive"))
      (node (ref "EPS/OBC") (pin "P$15") (pinfunction "15_P$15") (pintype "passive"))
      (node (ref "EPS/OBC") (pin "P$16") (pinfunction "16_P$16") (pintype "passive"))
      (node (ref "FAB") (pin "P$15") (pinfunction "15_P$15") (pintype "passive"))
      (node (ref "FAB") (pin "P$16") (pinfunction "16_P$16") (pintype "passive"))
      (node (ref "MSN_I") (pin "P$15") (pinfunction "15_P$15") (pintype "passive"))
      (node (ref "MSN_I") (pin "P$16") (pinfunction "16_P$16") (pintype "passive"))
      (node (ref "MSN_II") (pin "P$15") (pinfunction "15_P$15") (pintype "passive"))
      (node (ref "MSN_II") (pin "P$16") (pinfunction "16_P$16") (pintype "passive"))
      (node (ref "RAB") (pin "P$15") (pinfunction "15_P$15") (pintype "passive"))
      (node (ref "RAB") (pin "P$16") (pinfunction "16_P$16") (pintype "passive"))
    )
    (net (code "87") (name "SUP_3V3_1") (class "Default")
      (node (ref "C1") (pin "1") (pinfunction "1_1") (pintype "passive"))
      (node (ref "COM") (pin "P$49") (pinfunction "49_P$49") (pintype "passive"))
      (node (ref "COM") (pin "P$50") (pinfunction "50_P$50") (pintype "passive"))
      (node (ref "EPS/OBC") (pin "P$49") (pinfunction "49_P$49") (pintype "passive"))
      (node (ref "EPS/OBC") (pin "P$50") (pinfunction "50_P$50") (pintype "passive"))
      (node (ref "FAB") (pin "P$49") (pinfunction "49_P$49") (pintype "passive"))
      (node (ref "FAB") (pin "P$50") (pinfunction "50_P$50") (pintype "passive"))
      (node (ref "MSN_I") (pin "P$49") (pinfunction "49_P$49") (pintype "passive"))
      (node (ref "MSN_I") (pin "P$50") (pinfunction "50_P$50") (pintype "passive"))
      (node (ref "MSN_II") (pin "P$49") (pinfunction "49_P$49") (pintype "passive"))
      (node (ref "MSN_II") (pin "P$50") (pinfunction "50_P$50") (pintype "passive"))
      (node (ref "RAB") (pin "P$49") (pinfunction "49_P$49") (pintype "passive"))
      (node (ref "RAB") (pin "P$50") (pinfunction "50_P$50") (pintype "passive"))
      (node (ref "SP1/+Y") (pin "2") (pinfunction "2_2") (pintype "passive"))
      (node (ref "SP2/-Y") (pin "2") (pinfunction "2_2") (pintype "passive"))
      (node (ref "SP3/-X") (pin "2") (pinfunction "2_2") (pintype "passive"))
      (node (ref "SP4/+X") (pin "2") (pinfunction "2_2") (pintype "passive"))
      (node (ref "SP5/-Z") (pin "2") (pinfunction "2_2") (pintype "passive"))
      (node (ref "U$3") (pin "4") (pinfunction "VDD_4") (pintype "power_in"))
    )
    (net (code "88") (name "SUP_3V3_2") (class "Default")
      (node (ref "COM") (pin "P$25") (pinfunction "25_P$25") (pintype "passive"))
      (node (ref "COM") (pin "P$26") (pinfunction "26_P$26") (pintype "passive"))
      (node (ref "EPS/OBC") (pin "P$25") (pinfunction "25_P$25") (pintype "passive"))
      (node (ref "EPS/OBC") (pin "P$26") (pinfunction "26_P$26") (pintype "passive"))
      (node (ref "FAB") (pin "P$25") (pinfunction "25_P$25") (pintype "passive"))
      (node (ref "FAB") (pin "P$26") (pinfunction "26_P$26") (pintype "passive"))
      (node (ref "MSN_I") (pin "P$25") (pinfunction "25_P$25") (pintype "passive"))
      (node (ref "MSN_I") (pin "P$26") (pinfunction "26_P$26") (pintype "passive"))
      (node (ref "MSN_II") (pin "P$25") (pinfunction "25_P$25") (pintype "passive"))
      (node (ref "MSN_II") (pin "P$26") (pinfunction "26_P$26") (pintype "passive"))
      (node (ref "RAB") (pin "P$25") (pinfunction "25_P$25") (pintype "passive"))
      (node (ref "RAB") (pin "P$26") (pinfunction "26_P$26") (pintype "passive"))
    )
    (net (code "89") (name "SUP_UNREG_1") (class "Default")
      (node (ref "COM") (pin "P$23") (pinfunction "23_P$23") (pintype "passive"))
      (node (ref "COM") (pin "P$24") (pinfunction "24_P$24") (pintype "passive"))
      (node (ref "EPS/OBC") (pin "P$23") (pinfunction "23_P$23") (pintype "passive"))
      (node (ref "EPS/OBC") (pin "P$24") (pinfunction "24_P$24") (pintype "passive"))
      (node (ref "FAB") (pin "P$23") (pinfunction "23_P$23") (pintype "passive"))
      (node (ref "FAB") (pin "P$24") (pinfunction "24_P$24") (pintype "passive"))
      (node (ref "MSN_I") (pin "P$23") (pinfunction "23_P$23") (pintype "passive"))
      (node (ref "MSN_I") (pin "P$24") (pinfunction "24_P$24") (pintype "passive"))
      (node (ref "MSN_II") (pin "P$23") (pinfunction "23_P$23") (pintype "passive"))
      (node (ref "MSN_II") (pin "P$24") (pinfunction "24_P$24") (pintype "passive"))
      (node (ref "RAB") (pin "P$23") (pinfunction "23_P$23") (pintype "passive"))
      (node (ref "RAB") (pin "P$24") (pinfunction "24_P$24") (pintype "passive"))
    )
    (net (code "90") (name "SUP_UNREG_2") (class "Default")
      (node (ref "COM") (pin "P$35") (pinfunction "35_P$35") (pintype "passive"))
      (node (ref "COM") (pin "P$36") (pinfunction "36_P$36") (pintype "passive"))
      (node (ref "EPS/OBC") (pin "P$35") (pinfunction "35_P$35") (pintype "passive"))
      (node (ref "EPS/OBC") (pin "P$36") (pinfunction "36_P$36") (pintype "passive"))
      (node (ref "FAB") (pin "P$35") (pinfunction "35_P$35") (pintype "passive"))
      (node (ref "FAB") (pin "P$36") (pinfunction "36_P$36") (pintype "passive"))
      (node (ref "MSN_I") (pin "P$35") (pinfunction "35_P$35") (pintype "passive"))
      (node (ref "MSN_I") (pin "P$36") (pinfunction "36_P$36") (pintype "passive"))
      (node (ref "MSN_II") (pin "P$35") (pinfunction "35_P$35") (pintype "passive"))
      (node (ref "MSN_II") (pin "P$36") (pinfunction "36_P$36") (pintype "passive"))
      (node (ref "RAB") (pin "P$35") (pinfunction "35_P$35") (pintype "passive"))
      (node (ref "RAB") (pin "P$36") (pinfunction "36_P$36") (pintype "passive"))
      (node (ref "SP2/-Y") (pin "3") (pinfunction "3_3") (pintype "passive"))
    )
    (net (code "91") (name "TEMP1_+X_NEW") (class "Default")
      (node (ref "FAB") (pin "P$28") (pinfunction "28_P$28") (pintype "passive"))
      (node (ref "SP1/+Y") (pin "10") (pinfunction "10_10") (pintype "passive"))
    )
    (net (code "92") (name "TEMP2_-Y_NEW") (class "Default")
      (node (ref "FAB") (pin "P$22") (pinfunction "22_P$22") (pintype "passive"))
      (node (ref "SP4/+X") (pin "10") (pinfunction "10_10") (pintype "passive"))
    )
    (net (code "93") (name "TEMP3_-Z_NEW") (class "Default")
      (node (ref "FAB") (pin "P$34") (pinfunction "34_P$34") (pintype "passive"))
      (node (ref "SP5/-Z") (pin "10") (pinfunction "10_10") (pintype "passive"))
    )
    (net (code "94") (name "TEMP4_+Y_NEW") (class "Default")
      (node (ref "FAB") (pin "P$38") (pinfunction "38_P$38") (pintype "passive"))
      (node (ref "SP3/-X") (pin "10") (pinfunction "10_10") (pintype "passive"))
    )
    (net (code "95") (name "TEMP5_-X_NEW") (class "Default")
      (node (ref "FAB") (pin "P$32") (pinfunction "32_P$32") (pintype "passive"))
      (node (ref "SP2/-Y") (pin "10") (pinfunction "10_10") (pintype "passive"))
    )
    (net (code "96") (name "unconnected-(COM-1-PadP$1)") (class "Default")
      (node (ref "COM") (pin "P$1") (pinfunction "1_P$1") (pintype "passive"))
    )
    (net (code "97") (name "unconnected-(COM-2-PadP$2)") (class "Default")
      (node (ref "COM") (pin "P$2") (pinfunction "2_P$2") (pintype "passive"))
    )
    (net (code "98") (name "unconnected-(COM-3-PadP$3)") (class "Default")
      (node (ref "COM") (pin "P$3") (pinfunction "3_P$3") (pintype "passive"))
    )
    (net (code "99") (name "unconnected-(COM-4-PadP$4)") (class "Default")
      (node (ref "COM") (pin "P$4") (pinfunction "4_P$4") (pintype "passive"))
    )
    (net (code "100") (name "unconnected-(COM-5-PadP$5)") (class "Default")
      (node (ref "COM") (pin "P$5") (pinfunction "5_P$5") (pintype "passive"))
    )
    (net (code "101") (name "unconnected-(COM-6-PadP$6)") (class "Default")
      (node (ref "COM") (pin "P$6") (pinfunction "6_P$6") (pintype "passive"))
    )
    (net (code "102") (name "unconnected-(COM-17-PadP$17)") (class "Default")
      (node (ref "COM") (pin "P$17") (pinfunction "17_P$17") (pintype "passive"))
    )
    (net (code "103") (name "unconnected-(COM-18-PadP$18)") (class "Default")
      (node (ref "COM") (pin "P$18") (pinfunction "18_P$18") (pintype "passive"))
    )
    (net (code "104") (name "unconnected-(COM-19-PadP$19)") (class "Default")
      (node (ref "COM") (pin "P$19") (pinfunction "19_P$19") (pintype "passive"))
    )
    (net (code "105") (name "unconnected-(COM-20-PadP$20)") (class "Default")
      (node (ref "COM") (pin "P$20") (pinfunction "20_P$20") (pintype "passive"))
    )
    (net (code "106") (name "unconnected-(COM-29-PadP$29)") (class "Default")
      (node (ref "COM") (pin "P$29") (pinfunction "29_P$29") (pintype "passive"))
    )
    (net (code "107") (name "unconnected-(COM-30-PadP$30)") (class "Default")
      (node (ref "COM") (pin "P$30") (pinfunction "30_P$30") (pintype "passive"))
    )
    (net (code "108") (name "unconnected-(COM-39-PadP$39)") (class "Default")
      (node (ref "COM") (pin "P$39") (pinfunction "39_P$39") (pintype "passive"))
    )
    (net (code "109") (name "unconnected-(COM-40-PadP$40)") (class "Default")
      (node (ref "COM") (pin "P$40") (pinfunction "40_P$40") (pintype "passive"))
    )
    (net (code "110") (name "unconnected-(COM-41-PadP$41)") (class "Default")
      (node (ref "COM") (pin "P$41") (pinfunction "41_P$41") (pintype "passive"))
    )
    (net (code "111") (name "unconnected-(FAB-10-PadP$10)") (class "Default")
      (node (ref "FAB") (pin "P$10") (pinfunction "10_P$10") (pintype "passive"))
    )
    (net (code "112") (name "unconnected-(FAB-11-PadP$11)") (class "Default")
      (node (ref "FAB") (pin "P$11") (pinfunction "11_P$11") (pintype "passive"))
    )
    (net (code "113") (name "unconnected-(FAB-12-PadP$12)") (class "Default")
      (node (ref "FAB") (pin "P$12") (pinfunction "12_P$12") (pintype "passive"))
    )
    (net (code "114") (name "unconnected-(FAB-45-PadP$45)") (class "Default")
      (node (ref "FAB") (pin "P$45") (pinfunction "45_P$45") (pintype "passive"))
    )
    (net (code "115") (name "unconnected-(FAB-46-PadP$46)") (class "Default")
      (node (ref "FAB") (pin "P$46") (pinfunction "46_P$46") (pintype "passive"))
    )
    (net (code "116") (name "unconnected-(FAB-47-PadP$47)") (class "Default")
      (node (ref "FAB") (pin "P$47") (pinfunction "47_P$47") (pintype "passive"))
    )
    (net (code "117") (name "unconnected-(FAB-48-PadP$48)") (class "Default")
      (node (ref "FAB") (pin "P$48") (pinfunction "48_P$48") (pintype "passive"))
    )
    (net (code "118") (name "unconnected-(MSN_I-1-PadP$1)") (class "Default")
      (node (ref "MSN_I") (pin "P$1") (pinfunction "1_P$1") (pintype "passive"))
    )
    (net (code "119") (name "unconnected-(MSN_I-2-PadP$2)") (class "Default")
      (node (ref "MSN_I") (pin "P$2") (pinfunction "2_P$2") (pintype "passive"))
    )
    (net (code "120") (name "unconnected-(MSN_I-3-PadP$3)") (class "Default")
      (node (ref "MSN_I") (pin "P$3") (pinfunction "3_P$3") (pintype "passive"))
    )
    (net (code "121") (name "unconnected-(MSN_I-5-PadP$5)") (class "Default")
      (node (ref "MSN_I") (pin "P$5") (pinfunction "5_P$5") (pintype "passive"))
    )
    (net (code "122") (name "unconnected-(MSN_I-6-PadP$6)") (class "Default")
      (node (ref "MSN_I") (pin "P$6") (pinfunction "6_P$6") (pintype "passive"))
    )
    (net (code "123") (name "unconnected-(MSN_I-41-PadP$41)") (class "Default")
      (node (ref "MSN_I") (pin "P$41") (pinfunction "41_P$41") (pintype "passive"))
    )
    (net (code "124") (name "unconnected-(MSN_I-46-PadP$46)") (class "Default")
      (node (ref "MSN_I") (pin "P$46") (pinfunction "46_P$46") (pintype "passive"))
    )
    (net (code "125") (name "unconnected-(RAB-44-PadP$44)") (class "Default")
      (node (ref "RAB") (pin "P$44") (pinfunction "44_P$44") (pintype "passive"))
    )
    (net (code "126") (name "unconnected-(RAB-45-PadP$45)") (class "Default")
      (node (ref "RAB") (pin "P$45") (pinfunction "45_P$45") (pintype "passive"))
    )
    (net (code "127") (name "unconnected-(SP1/+Y-Pad3)") (class "Default")
      (node (ref "SP1/+Y") (pin "3") (pinfunction "3_3") (pintype "passive"))
    )
    (net (code "128") (name "unconnected-(SP1/+Y-Pad4)") (class "Default")
      (node (ref "SP1/+Y") (pin "4") (pinfunction "4_4") (pintype "passive"))
    )
    (net (code "129") (name "unconnected-(SP1/+Y-Pad5)") (class "Default")
      (node (ref "SP1/+Y") (pin "5") (pinfunction "5_5") (pintype "passive"))
    )
    (net (code "130") (name "unconnected-(SP1/+Y-Pad6)") (class "Default")
      (node (ref "SP1/+Y") (pin "6") (pinfunction "6_6") (pintype "passive"))
    )
    (net (code "131") (name "unconnected-(SP1/+Y-Pad7)") (class "Default")
      (node (ref "SP1/+Y") (pin "7") (pinfunction "7_7") (pintype "passive"))
    )
    (net (code "132") (name "unconnected-(SP1/+Y-Pad11)") (class "Default")
      (node (ref "SP1/+Y") (pin "11") (pinfunction "11_11") (pintype "passive"))
    )
    (net (code "133") (name "unconnected-(SP3/-X-Pad3)") (class "Default")
      (node (ref "SP3/-X") (pin "3") (pinfunction "3_3") (pintype "passive"))
    )
    (net (code "134") (name "unconnected-(SP3/-X-Pad4)") (class "Default")
      (node (ref "SP3/-X") (pin "4") (pinfunction "4_4") (pintype "passive"))
    )
    (net (code "135") (name "unconnected-(SP3/-X-Pad5)") (class "Default")
      (node (ref "SP3/-X") (pin "5") (pinfunction "5_5") (pintype "passive"))
    )
    (net (code "136") (name "unconnected-(SP3/-X-Pad11)") (class "Default")
      (node (ref "SP3/-X") (pin "11") (pinfunction "11_11") (pintype "passive"))
    )
    (net (code "137") (name "unconnected-(SP4/+X-Pad3)") (class "Default")
      (node (ref "SP4/+X") (pin "3") (pinfunction "3_3") (pintype "passive"))
    )
    (net (code "138") (name "unconnected-(SP4/+X-Pad4)") (class "Default")
      (node (ref "SP4/+X") (pin "4") (pinfunction "4_4") (pintype "passive"))
    )
    (net (code "139") (name "unconnected-(SP4/+X-Pad5)") (class "Default")
      (node (ref "SP4/+X") (pin "5") (pinfunction "5_5") (pintype "passive"))
    )
    (net (code "140") (name "unconnected-(SP4/+X-Pad11)") (class "Default")
      (node (ref "SP4/+X") (pin "11") (pinfunction "11_11") (pintype "passive"))
    )
    (net (code "141") (name "unconnected-(SP5/-Z-Pad3)") (class "Default")
      (node (ref "SP5/-Z") (pin "3") (pinfunction "3_3") (pintype "passive"))
    )
    (net (code "142") (name "unconnected-(SP5/-Z-Pad4)") (class "Default")
      (node (ref "SP5/-Z") (pin "4") (pinfunction "4_4") (pintype "passive"))
    )
    (net (code "143") (name "unconnected-(SP5/-Z-Pad5)") (class "Default")
      (node (ref "SP5/-Z") (pin "5") (pinfunction "5_5") (pintype "passive"))
    )
    (net (code "144") (name "unconnected-(SP5/-Z-Pad11)") (class "Default")
      (node (ref "SP5/-Z") (pin "11") (pinfunction "11_11") (pintype "passive"))
    )
    (net (code "145") (name "unconnected-(SW3-P$2-Pad2)") (class "Default")
      (node (ref "SW3") (pin "2") (pinfunction "P$2_2") (pintype "bidirectional"))
    )
  )
)
